# 1_micro.net
KiCad netlist of a schematic drawn in Altium Designer
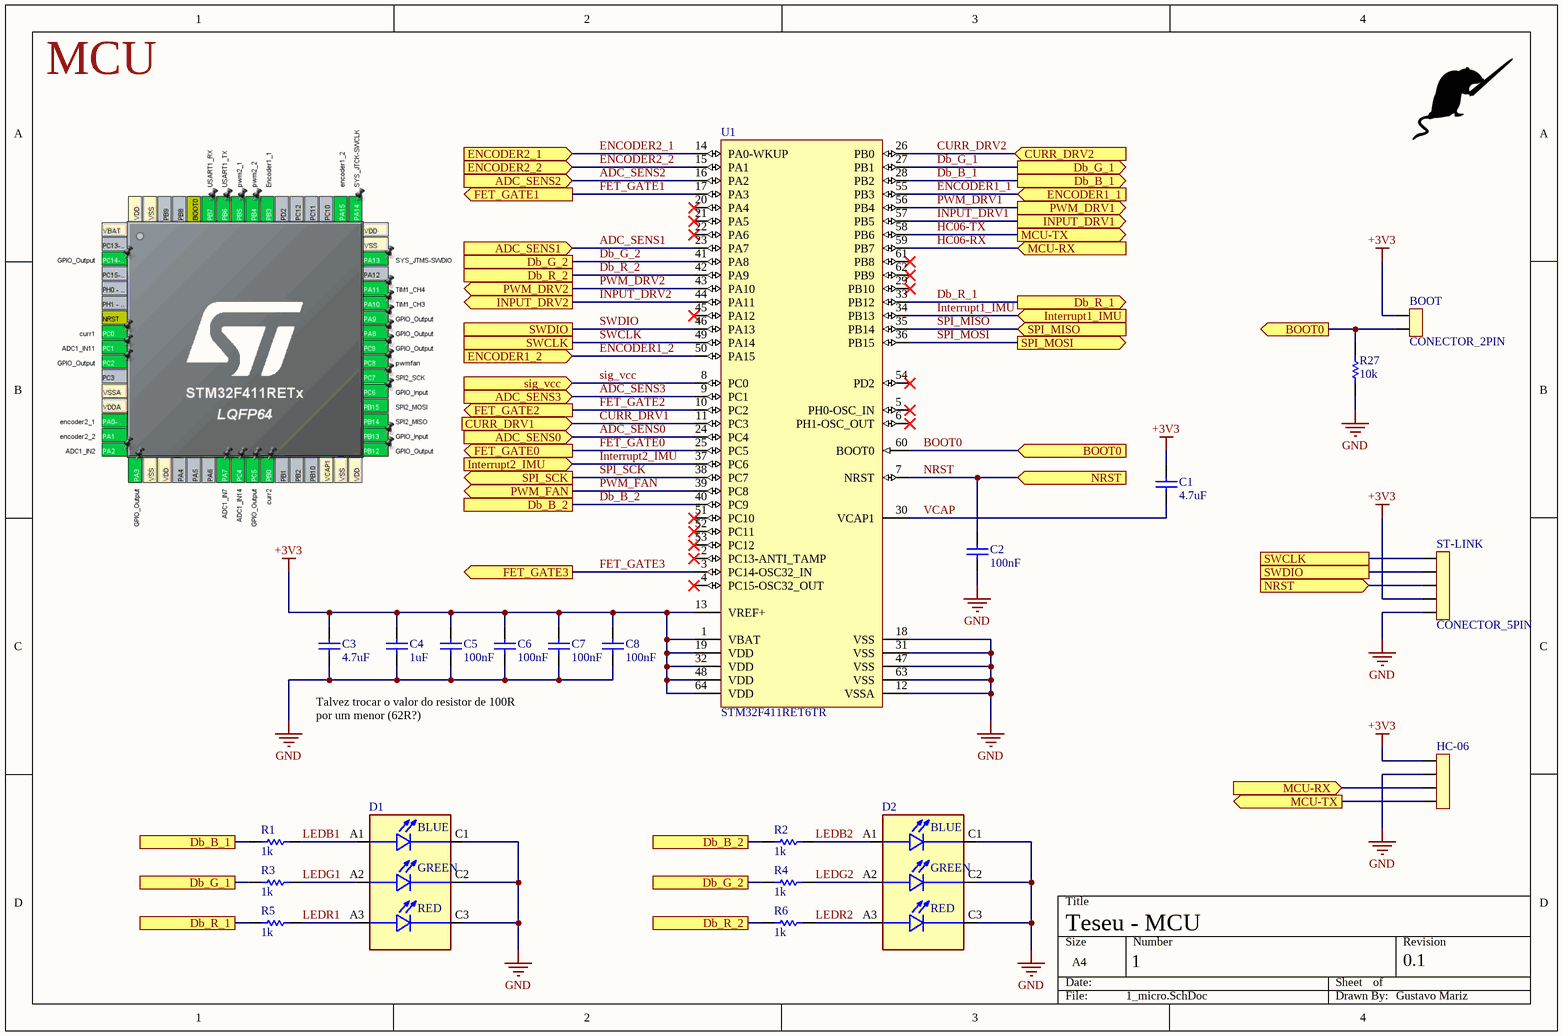
[diagram p0: 1_micro.SchDoc]

(export (version "E")
  (design (tool "Eeschema 10.0.6"))
  (components
    (comp (ref "BOOT")
      (value "CONECTOR_2PIN")
      (footprint "CON2")
      (libsource (lib "Biblioteca Trincabotz (1)") (part "CONECTOR_2PIN"))
    )
    (comp (ref "C1")
      (value "CAP")
      (footprint "0603")
      (description "Capacitor")
      (fields (field (name "VALOR") "4.7uF"))
      (libsource (lib "Biblioteca Trincabotz (1)") (part "CAP. CERÂMICO"))
    )
    (comp (ref "C2")
      (value "CAP")
      (footprint "0603")
      (description "Capacitor")
      (fields (field (name "VALOR") "100nF"))
      (libsource (lib "Biblioteca Trincabotz (1)") (part "CAP. CERÂMICO"))
    )
    (comp (ref "C3")
      (value "CAP")
      (footprint "0603")
      (description "Capacitor")
      (fields (field (name "VALOR") "4.7uF"))
      (libsource (lib "Biblioteca Trincabotz (1)") (part "CAP. CERÂMICO"))
    )
    (comp (ref "C4")
      (value "CAP")
      (footprint "0603")
      (description "Capacitor")
      (fields (field (name "VALOR") "1uF"))
      (libsource (lib "Biblioteca Trincabotz (1)") (part "CAP. CERÂMICO"))
    )
    (comp (ref "C5")
      (value "CAP")
      (footprint "0603")
      (description "Capacitor")
      (fields (field (name "VALOR") "100nF"))
      (libsource (lib "Biblioteca Trincabotz (1)") (part "CAP. CERÂMICO"))
    )
    (comp (ref "C6")
      (value "CAP")
      (footprint "0603")
      (description "Capacitor")
      (fields (field (name "VALOR") "100nF"))
      (libsource (lib "Biblioteca Trincabotz (1)") (part "CAP. CERÂMICO"))
    )
    (comp (ref "C7")
      (value "CAP")
      (footprint "0603")
      (description "Capacitor")
      (fields (field (name "VALOR") "100nF"))
      (libsource (lib "Biblioteca Trincabotz (1)") (part "CAP. CERÂMICO"))
    )
    (comp (ref "C8")
      (value "CAP")
      (footprint "0603")
      (description "Capacitor")
      (fields (field (name "VALOR") "100nF"))
      (libsource (lib "Biblioteca Trincabotz (1)") (part "CAP. CERÂMICO"))
    )
    (comp (ref "D1")
      (value "KRTBLSLPS1.32-VUVX-EQ+BTBV-D8+TWTZ-L1-B")
      (footprint "LED_KRTBLSLPS1.32-VUVX-EQ+BTBV-D8+TWTZ-L1-B")
      (fields (field (name "MF") "OSRAM Opto Semiconductors Inc."))
      (libsource (lib "KRTBLSLPS1.32-VUVX-EQ_BTBV-D8_TWTZ-L1-B") (part "KRTBLSLPS1.32-VUVX-EQ+BTBV-D8+TWTZ-L1-B"))
    )
    (comp (ref "D2")
      (value "KRTBLSLPS1.32-VUVX-EQ+BTBV-D8+TWTZ-L1-B")
      (footprint "LED_KRTBLSLPS1.32-VUVX-EQ+BTBV-D8+TWTZ-L1-B")
      (fields (field (name "MF") "OSRAM Opto Semiconductors Inc."))
      (libsource (lib "KRTBLSLPS1.32-VUVX-EQ_BTBV-D8_TWTZ-L1-B") (part "KRTBLSLPS1.32-VUVX-EQ+BTBV-D8+TWTZ-L1-B"))
    )
    (comp (ref "HC-06")
      (value "~")
      (footprint "CON4")
      (libsource (lib "Biblioteca Trincabotz (1)") (part "CONECTOR_4PIN"))
    )
    (comp (ref "R1")
      (value "1k")
      (footprint "RES 0603")
      (description "Resistor")
      (fields (field (name "Comment") "RESISTOR"))
      (libsource (lib "Biblioteca Trincabotz (1)") (part "RESISTOR"))
    )
    (comp (ref "R2")
      (value "1k")
      (footprint "RES 0603")
      (description "Resistor")
      (fields (field (name "Comment") "RESISTOR"))
      (libsource (lib "Biblioteca Trincabotz (1)") (part "RESISTOR"))
    )
    (comp (ref "R3")
      (value "1k")
      (footprint "RES 0603")
      (description "Resistor")
      (fields (field (name "Comment") "RESISTOR"))
      (libsource (lib "Biblioteca Trincabotz (1)") (part "RESISTOR"))
    )
    (comp (ref "R4")
      (value "1k")
      (footprint "RES 0603")
      (description "Resistor")
      (fields (field (name "Comment") "RESISTOR"))
      (libsource (lib "Biblioteca Trincabotz (1)") (part "RESISTOR"))
    )
    (comp (ref "R5")
      (value "1k")
      (footprint "RES 0603")
      (description "Resistor")
      (fields (field (name "Comment") "RESISTOR"))
      (libsource (lib "Biblioteca Trincabotz (1)") (part "RESISTOR"))
    )
    (comp (ref "R6")
      (value "1k")
      (footprint "RES 0603")
      (description "Resistor")
      (fields (field (name "Comment") "RESISTOR"))
      (libsource (lib "Biblioteca Trincabotz (1)") (part "RESISTOR"))
    )
    (comp (ref "R27")
      (value "10k")
      (footprint "RES 0805")
      (description "Resistor")
      (fields (field (name "Comment") "RESISTOR"))
      (libsource (lib "Biblioteca Trincabotz (1)") (part "RESISTOR"))
    )
    (comp (ref "ST-LINK")
      (value "CONECTOR_5PIN")
      (footprint "CON5")
      (libsource (lib "Biblioteca Trincabotz (1)") (part "CONECTOR_5PIN"))
    )
    (comp (ref "U1")
      (value "STM32F411RET6TR")
      (footprint "STM-LQFP64_L")
      (libsource (lib "Altium Content Vault") (part "MC-ARM-STM32F411-LQFP64"))
    )
  )
  (nets
    (net (code "1") (name "+3V3") (class "Default")
      (node (ref "BOOT") (pin "2") (pinfunction "2_2") (pintype "passive"))
      (node (ref "C1") (pin "2") (pinfunction "2_2") (pintype "passive"))
      (node (ref "C3") (pin "2") (pinfunction "2_2") (pintype "passive"))
      (node (ref "C4") (pin "2") (pinfunction "2_2") (pintype "passive"))
      (node (ref "C5") (pin "2") (pinfunction "2_2") (pintype "passive"))
      (node (ref "C6") (pin "2") (pinfunction "2_2") (pintype "passive"))
      (node (ref "C7") (pin "2") (pinfunction "2_2") (pintype "passive"))
      (node (ref "C8") (pin "2") (pinfunction "2_2") (pintype "passive"))
      (node (ref "HC-06") (pin "4") (pinfunction "4_4") (pintype "passive"))
      (node (ref "ST-LINK") (pin "2") (pinfunction "2_2") (pintype "passive"))
      (node (ref "U1") (pin "1") (pinfunction "VBAT_1") (pintype "power_in"))
      (node (ref "U1") (pin "13") (pinfunction "VREF+_13") (pintype "power_in"))
      (node (ref "U1") (pin "19") (pinfunction "VDD_19") (pintype "power_in"))
      (node (ref "U1") (pin "32") (pinfunction "VDD_32") (pintype "power_in"))
      (node (ref "U1") (pin "48") (pinfunction "VDD_48") (pintype "power_in"))
      (node (ref "U1") (pin "64") (pinfunction "VDD_64") (pintype "power_in"))
    )
    (net (code "2") (name "/ADC_SENS0") (class "Default")
      (node (ref "U1") (pin "24") (pinfunction "PC4_24") (pintype "bidirectional"))
    )
    (net (code "3") (name "/ADC_SENS1") (class "Default")
      (node (ref "U1") (pin "23") (pinfunction "PA7_23") (pintype "bidirectional"))
    )
    (net (code "4") (name "/ADC_SENS2") (class "Default")
      (node (ref "U1") (pin "16") (pinfunction "PA2_16") (pintype "bidirectional"))
    )
    (net (code "5") (name "/ADC_SENS3") (class "Default")
      (node (ref "U1") (pin "9") (pinfunction "PC1_9") (pintype "bidirectional"))
    )
    (net (code "6") (name "/BOOT0") (class "Default")
      (node (ref "BOOT") (pin "1") (pinfunction "1_1") (pintype "passive"))
      (node (ref "R27") (pin "2") (pinfunction "2_2") (pintype "passive"))
      (node (ref "U1") (pin "60") (pinfunction "BOOT0_60") (pintype "input"))
    )
    (net (code "7") (name "/CURR_DRV1") (class "Default")
      (node (ref "U1") (pin "11") (pinfunction "PC3_11") (pintype "bidirectional"))
    )
    (net (code "8") (name "/CURR_DRV2") (class "Default")
      (node (ref "U1") (pin "26") (pinfunction "PB0_26") (pintype "bidirectional"))
    )
    (net (code "9") (name "/Db_B_1") (class "Default")
      (node (ref "R1") (pin "1") (pinfunction "1_1") (pintype "passive"))
      (node (ref "U1") (pin "28") (pinfunction "PB2_28") (pintype "bidirectional"))
    )
    (net (code "10") (name "/Db_B_2") (class "Default")
      (node (ref "R2") (pin "1") (pinfunction "1_1") (pintype "passive"))
      (node (ref "U1") (pin "40") (pinfunction "PC9_40") (pintype "bidirectional"))
    )
    (net (code "11") (name "/Db_G_1") (class "Default")
      (node (ref "R3") (pin "1") (pinfunction "1_1") (pintype "passive"))
      (node (ref "U1") (pin "27") (pinfunction "PB1_27") (pintype "bidirectional"))
    )
    (net (code "12") (name "/Db_G_2") (class "Default")
      (node (ref "R4") (pin "1") (pinfunction "1_1") (pintype "passive"))
      (node (ref "U1") (pin "41") (pinfunction "PA8_41") (pintype "bidirectional"))
    )
    (net (code "13") (name "/Db_R_1") (class "Default")
      (node (ref "R5") (pin "1") (pinfunction "1_1") (pintype "passive"))
      (node (ref "U1") (pin "33") (pinfunction "PB12_33") (pintype "bidirectional"))
    )
    (net (code "14") (name "/Db_R_2") (class "Default")
      (node (ref "R6") (pin "1") (pinfunction "1_1") (pintype "passive"))
      (node (ref "U1") (pin "42") (pinfunction "PA9_42") (pintype "bidirectional"))
    )
    (net (code "15") (name "/ENCODER1_1") (class "Default")
      (node (ref "U1") (pin "55") (pinfunction "PB3_55") (pintype "bidirectional"))
    )
    (net (code "16") (name "/ENCODER1_2") (class "Default")
      (node (ref "U1") (pin "50") (pinfunction "PA15_50") (pintype "bidirectional"))
    )
    (net (code "17") (name "/ENCODER2_1") (class "Default")
      (node (ref "U1") (pin "14") (pinfunction "PA0-WKUP_14") (pintype "bidirectional"))
    )
    (net (code "18") (name "/ENCODER2_2") (class "Default")
      (node (ref "U1") (pin "15") (pinfunction "PA1_15") (pintype "bidirectional"))
    )
    (net (code "19") (name "/FET_GATE0") (class "Default")
      (node (ref "U1") (pin "25") (pinfunction "PC5_25") (pintype "bidirectional"))
    )
    (net (code "20") (name "/FET_GATE1") (class "Default")
      (node (ref "U1") (pin "17") (pinfunction "PA3_17") (pintype "bidirectional"))
    )
    (net (code "21") (name "/FET_GATE2") (class "Default")
      (node (ref "U1") (pin "10") (pinfunction "PC2_10") (pintype "bidirectional"))
    )
    (net (code "22") (name "/FET_GATE3") (class "Default")
      (node (ref "U1") (pin "3") (pinfunction "PC14-OSC32_IN_3") (pintype "bidirectional"))
    )
    (net (code "23") (name "/HC06-RX") (class "Default")
      (node (ref "HC-06") (pin "2") (pinfunction "2_2") (pintype "passive"))
      (node (ref "U1") (pin "59") (pinfunction "PB7_59") (pintype "bidirectional"))
    )
    (net (code "24") (name "/HC06-TX") (class "Default")
      (node (ref "HC-06") (pin "1") (pinfunction "1_1") (pintype "passive"))
      (node (ref "U1") (pin "58") (pinfunction "PB6_58") (pintype "bidirectional"))
    )
    (net (code "25") (name "/INPUT_DRV1") (class "Default")
      (node (ref "U1") (pin "57") (pinfunction "PB5_57") (pintype "bidirectional"))
    )
    (net (code "26") (name "/INPUT_DRV2") (class "Default")
      (node (ref "U1") (pin "44") (pinfunction "PA11_44") (pintype "bidirectional"))
    )
    (net (code "27") (name "/Interrupt1_IMU") (class "Default")
      (node (ref "U1") (pin "34") (pinfunction "PB13_34") (pintype "bidirectional"))
    )
    (net (code "28") (name "/Interrupt2_IMU") (class "Default")
      (node (ref "U1") (pin "37") (pinfunction "PC6_37") (pintype "bidirectional"))
    )
    (net (code "29") (name "/LEDB1") (class "Default")
      (node (ref "D1") (pin "A1") (pinfunction "ANODE_BLUE_A1") (pintype "passive"))
      (node (ref "R1") (pin "2") (pinfunction "2_2") (pintype "passive"))
    )
    (net (code "30") (name "/LEDB2") (class "Default")
      (node (ref "D2") (pin "A1") (pinfunction "ANODE_BLUE_A1") (pintype "passive"))
      (node (ref "R2") (pin "2") (pinfunction "2_2") (pintype "passive"))
    )
    (net (code "31") (name "/LEDG1") (class "Default")
      (node (ref "D1") (pin "A2") (pinfunction "ANODE_TRUE_GREEN_A2") (pintype "passive"))
      (node (ref "R3") (pin "2") (pinfunction "2_2") (pintype "passive"))
    )
    (net (code "32") (name "/LEDG2") (class "Default")
      (node (ref "D2") (pin "A2") (pinfunction "ANODE_TRUE_GREEN_A2") (pintype "passive"))
      (node (ref "R4") (pin "2") (pinfunction "2_2") (pintype "passive"))
    )
    (net (code "33") (name "/LEDR1") (class "Default")
      (node (ref "D1") (pin "A3") (pinfunction "ANODE_RED_A3") (pintype "passive"))
      (node (ref "R5") (pin "2") (pinfunction "2_2") (pintype "passive"))
    )
    (net (code "34") (name "/LEDR2") (class "Default")
      (node (ref "D2") (pin "A3") (pinfunction "ANODE_RED_A3") (pintype "passive"))
      (node (ref "R6") (pin "2") (pinfunction "2_2") (pintype "passive"))
    )
    (net (code "35") (name "/NRST") (class "Default")
      (node (ref "C2") (pin "2") (pinfunction "2_2") (pintype "passive"))
      (node (ref "ST-LINK") (pin "3") (pinfunction "3_3") (pintype "passive"))
      (node (ref "U1") (pin "7") (pinfunction "NRST_7") (pintype "bidirectional"))
    )
    (net (code "36") (name "/PWM_DRV1") (class "Default")
      (node (ref "U1") (pin "56") (pinfunction "PB4_56") (pintype "bidirectional"))
    )
    (net (code "37") (name "/PWM_DRV2") (class "Default")
      (node (ref "U1") (pin "43") (pinfunction "PA10_43") (pintype "bidirectional"))
    )
    (net (code "38") (name "/PWM_FAN") (class "Default")
      (node (ref "U1") (pin "39") (pinfunction "PC8_39") (pintype "bidirectional"))
    )
    (net (code "39") (name "/SPI_MISO") (class "Default")
      (node (ref "U1") (pin "35") (pinfunction "PB14_35") (pintype "bidirectional"))
    )
    (net (code "40") (name "/SPI_MOSI") (class "Default")
      (node (ref "U1") (pin "36") (pinfunction "PB15_36") (pintype "bidirectional"))
    )
    (net (code "41") (name "/SPI_SCK") (class "Default")
      (node (ref "U1") (pin "38") (pinfunction "PC7_38") (pintype "bidirectional"))
    )
    (net (code "42") (name "/SWCLK") (class "Default")
      (node (ref "ST-LINK") (pin "5") (pinfunction "5_5") (pintype "passive"))
      (node (ref "U1") (pin "49") (pinfunction "PA14_49") (pintype "bidirectional"))
    )
    (net (code "43") (name "/SWDIO") (class "Default")
      (node (ref "ST-LINK") (pin "4") (pinfunction "4_4") (pintype "passive"))
      (node (ref "U1") (pin "46") (pinfunction "PA13_46") (pintype "bidirectional"))
    )
    (net (code "44") (name "/VCAP") (class "Default")
      (node (ref "C1") (pin "1") (pinfunction "1_1") (pintype "passive"))
      (node (ref "U1") (pin "30") (pinfunction "VCAP1_30") (pintype "passive"))
    )
    (net (code "45") (name "/sig_vcc") (class "Default")
      (node (ref "U1") (pin "8") (pinfunction "PC0_8") (pintype "bidirectional"))
    )
    (net (code "46") (name "GND") (class "Default")
      (node (ref "C2") (pin "1") (pinfunction "1_1") (pintype "passive"))
      (node (ref "C3") (pin "1") (pinfunction "1_1") (pintype "passive"))
      (node (ref "C4") (pin "1") (pinfunction "1_1") (pintype "passive"))
      (node (ref "C5") (pin "1") (pinfunction "1_1") (pintype "passive"))
      (node (ref "C6") (pin "1") (pinfunction "1_1") (pintype "passive"))
      (node (ref "C7") (pin "1") (pinfunction "1_1") (pintype "passive"))
      (node (ref "C8") (pin "1") (pinfunction "1_1") (pintype "passive"))
      (node (ref "D1") (pin "C1") (pinfunction "CATHODE_BLUE_C1") (pintype "passive"))
      (node (ref "D1") (pin "C2") (pinfunction "CATHODE_TRUE_GREEN_C2") (pintype "passive"))
      (node (ref "D1") (pin "C3") (pinfunction "CATHODE_RED_C3") (pintype "passive"))
      (node (ref "D2") (pin "C1") (pinfunction "CATHODE_BLUE_C1") (pintype "passive"))
      (node (ref "D2") (pin "C2") (pinfunction "CATHODE_TRUE_GREEN_C2") (pintype "passive"))
      (node (ref "D2") (pin "C3") (pinfunction "CATHODE_RED_C3") (pintype "passive"))
      (node (ref "HC-06") (pin "3") (pinfunction "3_3") (pintype "passive"))
      (node (ref "R27") (pin "1") (pinfunction "1_1") (pintype "passive"))
      (node (ref "ST-LINK") (pin "1") (pinfunction "1_1") (pintype "passive"))
      (node (ref "U1") (pin "12") (pinfunction "VSSA_12") (pintype "power_in"))
      (node (ref "U1") (pin "18") (pinfunction "VSS_18") (pintype "power_in"))
      (node (ref "U1") (pin "31") (pinfunction "VSS_31") (pintype "power_in"))
      (node (ref "U1") (pin "47") (pinfunction "VSS_47") (pintype "power_in"))
      (node (ref "U1") (pin "63") (pinfunction "VSS_63") (pintype "power_in"))
    )
    (net (code "47") (name "unconnected-(U1-PA4-Pad20)") (class "Default")
      (node (ref "U1") (pin "20") (pinfunction "PA4_20") (pintype "bidirectional+no_connect"))
    )
    (net (code "48") (name "unconnected-(U1-PA5-Pad21)") (class "Default")
      (node (ref "U1") (pin "21") (pinfunction "PA5_21") (pintype "bidirectional+no_connect"))
    )
    (net (code "49") (name "unconnected-(U1-PA6-Pad22)") (class "Default")
      (node (ref "U1") (pin "22") (pinfunction "PA6_22") (pintype "bidirectional+no_connect"))
    )
    (net (code "50") (name "unconnected-(U1-PA12-Pad45)") (class "Default")
      (node (ref "U1") (pin "45") (pinfunction "PA12_45") (pintype "bidirectional+no_connect"))
    )
    (net (code "51") (name "unconnected-(U1-PB8-Pad61)") (class "Default")
      (node (ref "U1") (pin "61") (pinfunction "PB8_61") (pintype "bidirectional+no_connect"))
    )
    (net (code "52") (name "unconnected-(U1-PB9-Pad62)") (class "Default")
      (node (ref "U1") (pin "62") (pinfunction "PB9_62") (pintype "bidirectional+no_connect"))
    )
    (net (code "53") (name "unconnected-(U1-PB10-Pad29)") (class "Default")
      (node (ref "U1") (pin "29") (pinfunction "PB10_29") (pintype "bidirectional+no_connect"))
    )
    (net (code "54") (name "unconnected-(U1-PC10-Pad51)") (class "Default")
      (node (ref "U1") (pin "51") (pinfunction "PC10_51") (pintype "bidirectional+no_connect"))
    )
    (net (code "55") (name "unconnected-(U1-PC11-Pad52)") (class "Default")
      (node (ref "U1") (pin "52") (pinfunction "PC11_52") (pintype "bidirectional+no_connect"))
    )
    (net (code "56") (name "unconnected-(U1-PC12-Pad53)") (class "Default")
      (node (ref "U1") (pin "53") (pinfunction "PC12_53") (pintype "bidirectional+no_connect"))
    )
    (net (code "57") (name "unconnected-(U1-PC13-ANTI_TAMP-Pad2)") (class "Default")
      (node (ref "U1") (pin "2") (pinfunction "PC13-ANTI_TAMP_2") (pintype "bidirectional+no_connect"))
    )
    (net (code "58") (name "unconnected-(U1-PC15-OSC32_OUT-Pad4)") (class "Default")
      (node (ref "U1") (pin "4") (pinfunction "PC15-OSC32_OUT_4") (pintype "bidirectional+no_connect"))
    )
    (net (code "59") (name "unconnected-(U1-PD2-Pad54)") (class "Default")
      (node (ref "U1") (pin "54") (pinfunction "PD2_54") (pintype "bidirectional+no_connect"))
    )
    (net (code "60") (name "unconnected-(U1-PH0-OSC_IN-Pad5)") (class "Default")
      (node (ref "U1") (pin "5") (pinfunction "PH0-OSC_IN_5") (pintype "bidirectional+no_connect"))
    )
    (net (code "61") (name "unconnected-(U1-PH1-OSC_OUT-Pad6)") (class "Default")
      (node (ref "U1") (pin "6") (pinfunction "PH1-OSC_OUT_6") (pintype "bidirectional+no_connect"))
    )
  )
)
